# Top-Level.net
KiCad netlist of a schematic drawn in Altium Designer
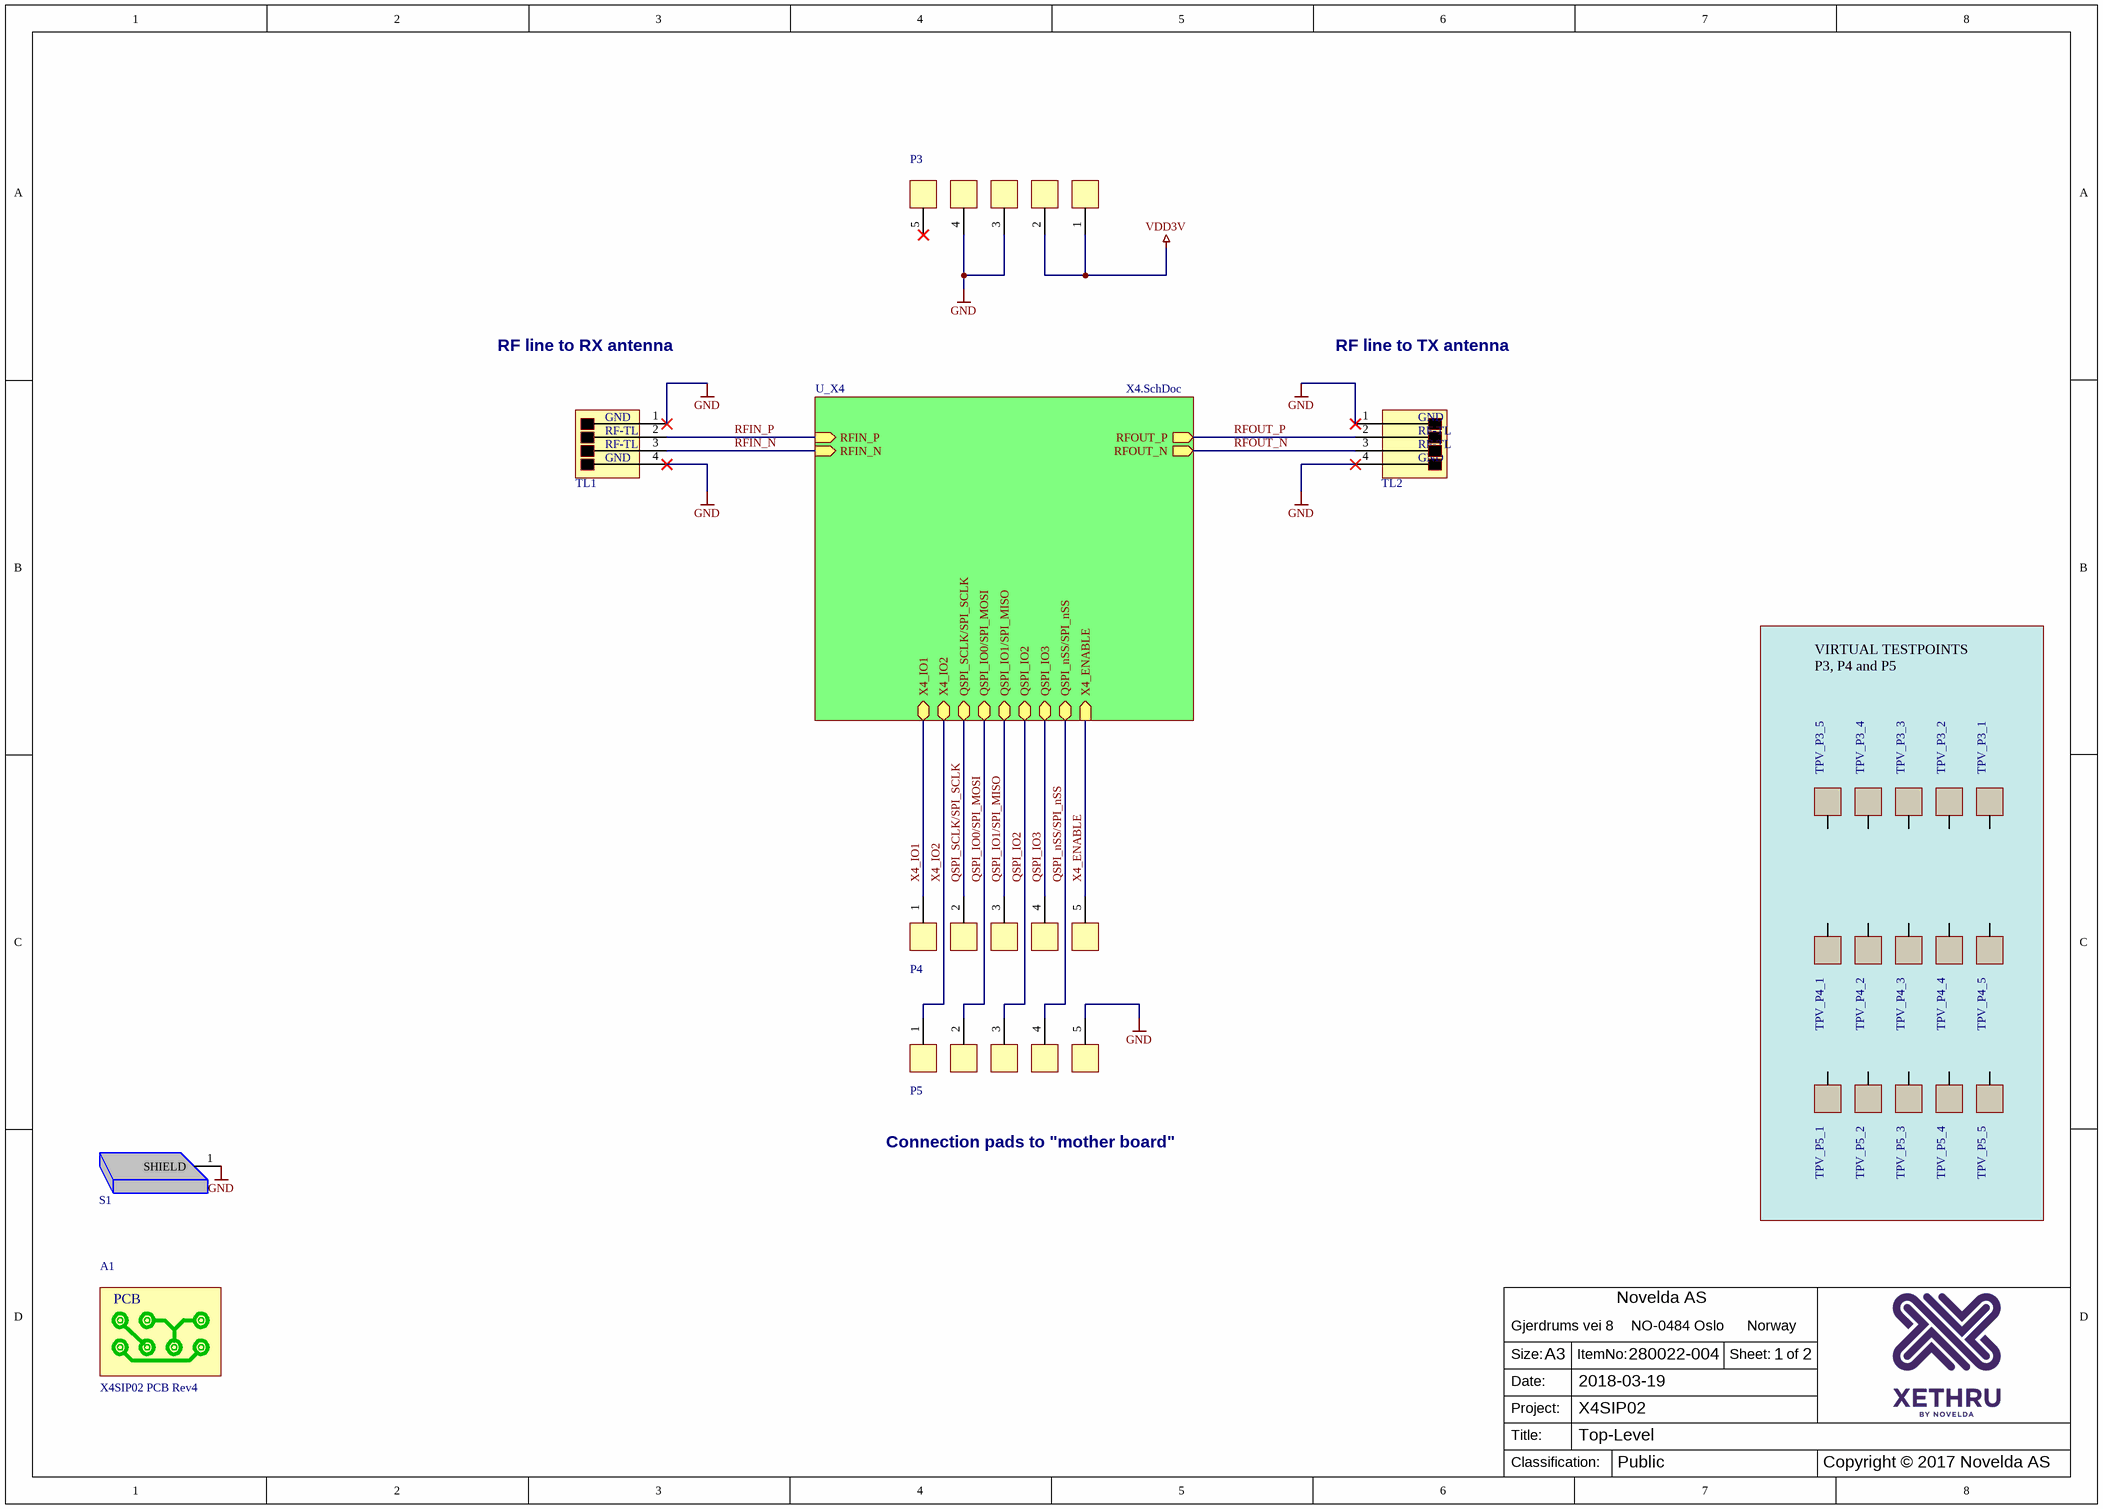
[diagram p0: Top-Level.SchDoc]

(export (version "E")
  (design (tool "Eeschema 10.0.6"))
  (components
    (comp (ref "A1")
      (value "X4SIP02 PCB Rev4")
      (fields (field (name "MANUFACTURER") "Novelda") (field (name "MPN") "290047-004"))
      (libsource (lib "novelda_altiumlib") (part "PCB-SYMBOL"))
    )
    (comp (ref "P3")
      (value "5x CONNECTION PADS")
      (footprint "ALTIUM-0024")
      (description "SMD CONNECTION PADS, 5, 0.6x0.6mm, 2mm PITCH")
      (fields (field (name "MANUFACTURER") "--"))
      (libsource (lib "novelda_altiumlib") (part "ALTIUM-0024"))
    )
    (comp (ref "P4")
      (value "5x CONNECTION PADS")
      (footprint "ALTIUM-0024")
      (description "SMD CONNECTION PADS, 5, 0.6x0.6mm, 2mm PITCH")
      (fields (field (name "MANUFACTURER") "--"))
      (libsource (lib "") (part "ALTIUM-0024_1"))
    )
    (comp (ref "P5")
      (value "5x CONNECTION PADS")
      (footprint "ALTIUM-0024")
      (description "SMD CONNECTION PADS, 5, 0.6x0.6mm, 2mm PITCH")
      (fields (field (name "MANUFACTURER") "--"))
      (libsource (lib "") (part "ALTIUM-0024_1"))
    )
    (comp (ref "S1")
      (value "Shield box")
      (footprint "200284-003")
      (description "Shieldbox 14.2 x 12.2 x 3mm")
      (fields (field (name "MANUFACTURER") "--"))
      (libsource (lib "novelda_altiumlib") (part "200284-003"))
    )
    (comp (ref "TL1")
      (value "X4SIP RF TRANSMISSION LINE")
      (fields (field (name "MANUFACTURER") "--"))
      (libsource (lib "novelda_altiumlib") (part "ALTIUM-0020"))
    )
    (comp (ref "TL2")
      (value "X4SIP RF TRANSMISSION LINE")
      (fields (field (name "MANUFACTURER") "--"))
      (libsource (lib "") (part "ALTIUM-0020_1"))
    )
    (comp (ref "TPV_P3_1")
      (value "TPV")
      (description "TESTPOINT, Virtual, Only on schematic, Used when actual testpoint is other component pins.")
      (libsource (lib "") (part "TESTPOINT-VIRTUAL_1"))
    )
    (comp (ref "TPV_P3_2")
      (value "TPV")
      (description "TESTPOINT, Virtual, Only on schematic, Used when actual testpoint is other component pins.")
      (libsource (lib "") (part "TESTPOINT-VIRTUAL_1"))
    )
    (comp (ref "TPV_P3_3")
      (value "TPV")
      (description "TESTPOINT, Virtual, Only on schematic, Used when actual testpoint is other component pins.")
      (libsource (lib "") (part "TESTPOINT-VIRTUAL_1"))
    )
    (comp (ref "TPV_P3_4")
      (value "TPV")
      (description "TESTPOINT, Virtual, Only on schematic, Used when actual testpoint is other component pins.")
      (libsource (lib "") (part "TESTPOINT-VIRTUAL_1"))
    )
    (comp (ref "TPV_P3_5")
      (value "TPV")
      (description "TESTPOINT, Virtual, Only on schematic, Used when actual testpoint is other component pins.")
      (libsource (lib "") (part "TESTPOINT-VIRTUAL_1"))
    )
    (comp (ref "TPV_P4_1")
      (value "TPV")
      (description "TESTPOINT, Virtual, Only on schematic, Used when actual testpoint is other component pins.")
      (libsource (lib "novelda_altiumlib") (part "TESTPOINT-VIRTUAL"))
    )
    (comp (ref "TPV_P4_2")
      (value "TPV")
      (description "TESTPOINT, Virtual, Only on schematic, Used when actual testpoint is other component pins.")
      (libsource (lib "novelda_altiumlib") (part "TESTPOINT-VIRTUAL"))
    )
    (comp (ref "TPV_P4_3")
      (value "TPV")
      (description "TESTPOINT, Virtual, Only on schematic, Used when actual testpoint is other component pins.")
      (libsource (lib "novelda_altiumlib") (part "TESTPOINT-VIRTUAL"))
    )
    (comp (ref "TPV_P4_4")
      (value "TPV")
      (description "TESTPOINT, Virtual, Only on schematic, Used when actual testpoint is other component pins.")
      (libsource (lib "novelda_altiumlib") (part "TESTPOINT-VIRTUAL"))
    )
    (comp (ref "TPV_P4_5")
      (value "TPV")
      (description "TESTPOINT, Virtual, Only on schematic, Used when actual testpoint is other component pins.")
      (libsource (lib "novelda_altiumlib") (part "TESTPOINT-VIRTUAL"))
    )
    (comp (ref "TPV_P5_1")
      (value "TPV")
      (description "TESTPOINT, Virtual, Only on schematic, Used when actual testpoint is other component pins.")
      (libsource (lib "novelda_altiumlib") (part "TESTPOINT-VIRTUAL"))
    )
    (comp (ref "TPV_P5_2")
      (value "TPV")
      (description "TESTPOINT, Virtual, Only on schematic, Used when actual testpoint is other component pins.")
      (libsource (lib "novelda_altiumlib") (part "TESTPOINT-VIRTUAL"))
    )
    (comp (ref "TPV_P5_3")
      (value "TPV")
      (description "TESTPOINT, Virtual, Only on schematic, Used when actual testpoint is other component pins.")
      (libsource (lib "novelda_altiumlib") (part "TESTPOINT-VIRTUAL"))
    )
    (comp (ref "TPV_P5_4")
      (value "TPV")
      (description "TESTPOINT, Virtual, Only on schematic, Used when actual testpoint is other component pins.")
      (libsource (lib "novelda_altiumlib") (part "TESTPOINT-VIRTUAL"))
    )
    (comp (ref "TPV_P5_5")
      (value "TPV")
      (description "TESTPOINT, Virtual, Only on schematic, Used when actual testpoint is other component pins.")
      (libsource (lib "novelda_altiumlib") (part "TESTPOINT-VIRTUAL"))
    )
  )
  (nets
    (net (code "1") (name "/QSPI_IO0{slash}SPI_MOSI") (class "Default")
      (node (ref "P5") (pin "2") (pinfunction "2_2") (pintype "passive"))
    )
    (net (code "2") (name "/QSPI_IO1{slash}SPI_MISO") (class "Default")
      (node (ref "P4") (pin "3") (pinfunction "3_3") (pintype "passive"))
    )
    (net (code "3") (name "/QSPI_IO2") (class "Default")
      (node (ref "P5") (pin "3") (pinfunction "3_3") (pintype "passive"))
    )
    (net (code "4") (name "/QSPI_IO3") (class "Default")
      (node (ref "P4") (pin "4") (pinfunction "4_4") (pintype "passive"))
    )
    (net (code "5") (name "/QSPI_SCLK{slash}SPI_SCLK") (class "Default")
      (node (ref "P4") (pin "2") (pinfunction "2_2") (pintype "passive"))
    )
    (net (code "6") (name "/QSPI_nSS{slash}SPI_nSS") (class "Default")
      (node (ref "P5") (pin "4") (pinfunction "4_4") (pintype "passive"))
    )
    (net (code "7") (name "/RFIN_N") (class "Default")
      (node (ref "TL1") (pin "3") (pinfunction "RF_N_3") (pintype "passive"))
    )
    (net (code "8") (name "/RFIN_P") (class "Default")
      (node (ref "TL1") (pin "2") (pinfunction "RF_P_2") (pintype "passive"))
    )
    (net (code "9") (name "/RFOUT_N") (class "Default")
      (node (ref "TL2") (pin "3") (pinfunction "RF_N_3") (pintype "passive"))
    )
    (net (code "10") (name "/RFOUT_P") (class "Default")
      (node (ref "TL2") (pin "2") (pinfunction "RF_P_2") (pintype "passive"))
    )
    (net (code "11") (name "/X4_ENABLE") (class "Default")
      (node (ref "P4") (pin "5") (pinfunction "5_5") (pintype "passive"))
    )
    (net (code "12") (name "/X4_IO1") (class "Default")
      (node (ref "P4") (pin "1") (pinfunction "1_1") (pintype "passive"))
    )
    (net (code "13") (name "/X4_IO2") (class "Default")
      (node (ref "P5") (pin "1") (pinfunction "1_1") (pintype "passive"))
    )
    (net (code "14") (name "GND") (class "Default")
      (node (ref "P3") (pin "3") (pinfunction "3_3") (pintype "passive"))
      (node (ref "P3") (pin "4") (pinfunction "4_4") (pintype "passive"))
      (node (ref "P5") (pin "5") (pinfunction "5_5") (pintype "passive"))
      (node (ref "S1") (pin "1") (pinfunction "SHIELD_1") (pintype "passive"))
      (node (ref "TL1") (pin "1") (pinfunction "GND_1") (pintype "passive"))
      (node (ref "TL1") (pin "4") (pinfunction "GND_4") (pintype "passive"))
      (node (ref "TL2") (pin "1") (pinfunction "GND_1") (pintype "passive"))
      (node (ref "TL2") (pin "4") (pinfunction "GND_4") (pintype "passive"))
    )
    (net (code "15") (name "VDD3V") (class "Default")
      (node (ref "P3") (pin "1") (pinfunction "1_1") (pintype "passive"))
      (node (ref "P3") (pin "2") (pinfunction "2_2") (pintype "passive"))
    )
    (net (code "16") (name "unconnected-(P3-Pad5)") (class "Default")
      (node (ref "P3") (pin "5") (pinfunction "5_5") (pintype "passive+no_connect"))
    )
    (net (code "17") (name "unconnected-(TPV_P3_1-Pad1)") (class "Default")
      (node (ref "TPV_P3_1") (pin "1") (pintype "passive"))
    )
    (net (code "18") (name "unconnected-(TPV_P3_2-Pad1)") (class "Default")
      (node (ref "TPV_P3_2") (pin "1") (pintype "passive"))
    )
    (net (code "19") (name "unconnected-(TPV_P3_3-Pad1)") (class "Default")
      (node (ref "TPV_P3_3") (pin "1") (pintype "passive"))
    )
    (net (code "20") (name "unconnected-(TPV_P3_4-Pad1)") (class "Default")
      (node (ref "TPV_P3_4") (pin "1") (pintype "passive"))
    )
    (net (code "21") (name "unconnected-(TPV_P3_5-Pad1)") (class "Default")
      (node (ref "TPV_P3_5") (pin "1") (pintype "passive"))
    )
    (net (code "22") (name "unconnected-(TPV_P4_1-Pad1)") (class "Default")
      (node (ref "TPV_P4_1") (pin "1") (pintype "passive"))
    )
    (net (code "23") (name "unconnected-(TPV_P4_2-Pad1)") (class "Default")
      (node (ref "TPV_P4_2") (pin "1") (pintype "passive"))
    )
    (net (code "24") (name "unconnected-(TPV_P4_3-Pad1)") (class "Default")
      (node (ref "TPV_P4_3") (pin "1") (pintype "passive"))
    )
    (net (code "25") (name "unconnected-(TPV_P4_4-Pad1)") (class "Default")
      (node (ref "TPV_P4_4") (pin "1") (pintype "passive"))
    )
    (net (code "26") (name "unconnected-(TPV_P4_5-Pad1)") (class "Default")
      (node (ref "TPV_P4_5") (pin "1") (pintype "passive"))
    )
    (net (code "27") (name "unconnected-(TPV_P5_1-Pad1)") (class "Default")
      (node (ref "TPV_P5_1") (pin "1") (pintype "passive"))
    )
    (net (code "28") (name "unconnected-(TPV_P5_2-Pad1)") (class "Default")
      (node (ref "TPV_P5_2") (pin "1") (pintype "passive"))
    )
    (net (code "29") (name "unconnected-(TPV_P5_3-Pad1)") (class "Default")
      (node (ref "TPV_P5_3") (pin "1") (pintype "passive"))
    )
    (net (code "30") (name "unconnected-(TPV_P5_4-Pad1)") (class "Default")
      (node (ref "TPV_P5_4") (pin "1") (pintype "passive"))
    )
    (net (code "31") (name "unconnected-(TPV_P5_5-Pad1)") (class "Default")
      (node (ref "TPV_P5_5") (pin "1") (pintype "passive"))
    )
  )
)
